# s4.net
KiCad netlist of a schematic drawn in Altium Designer
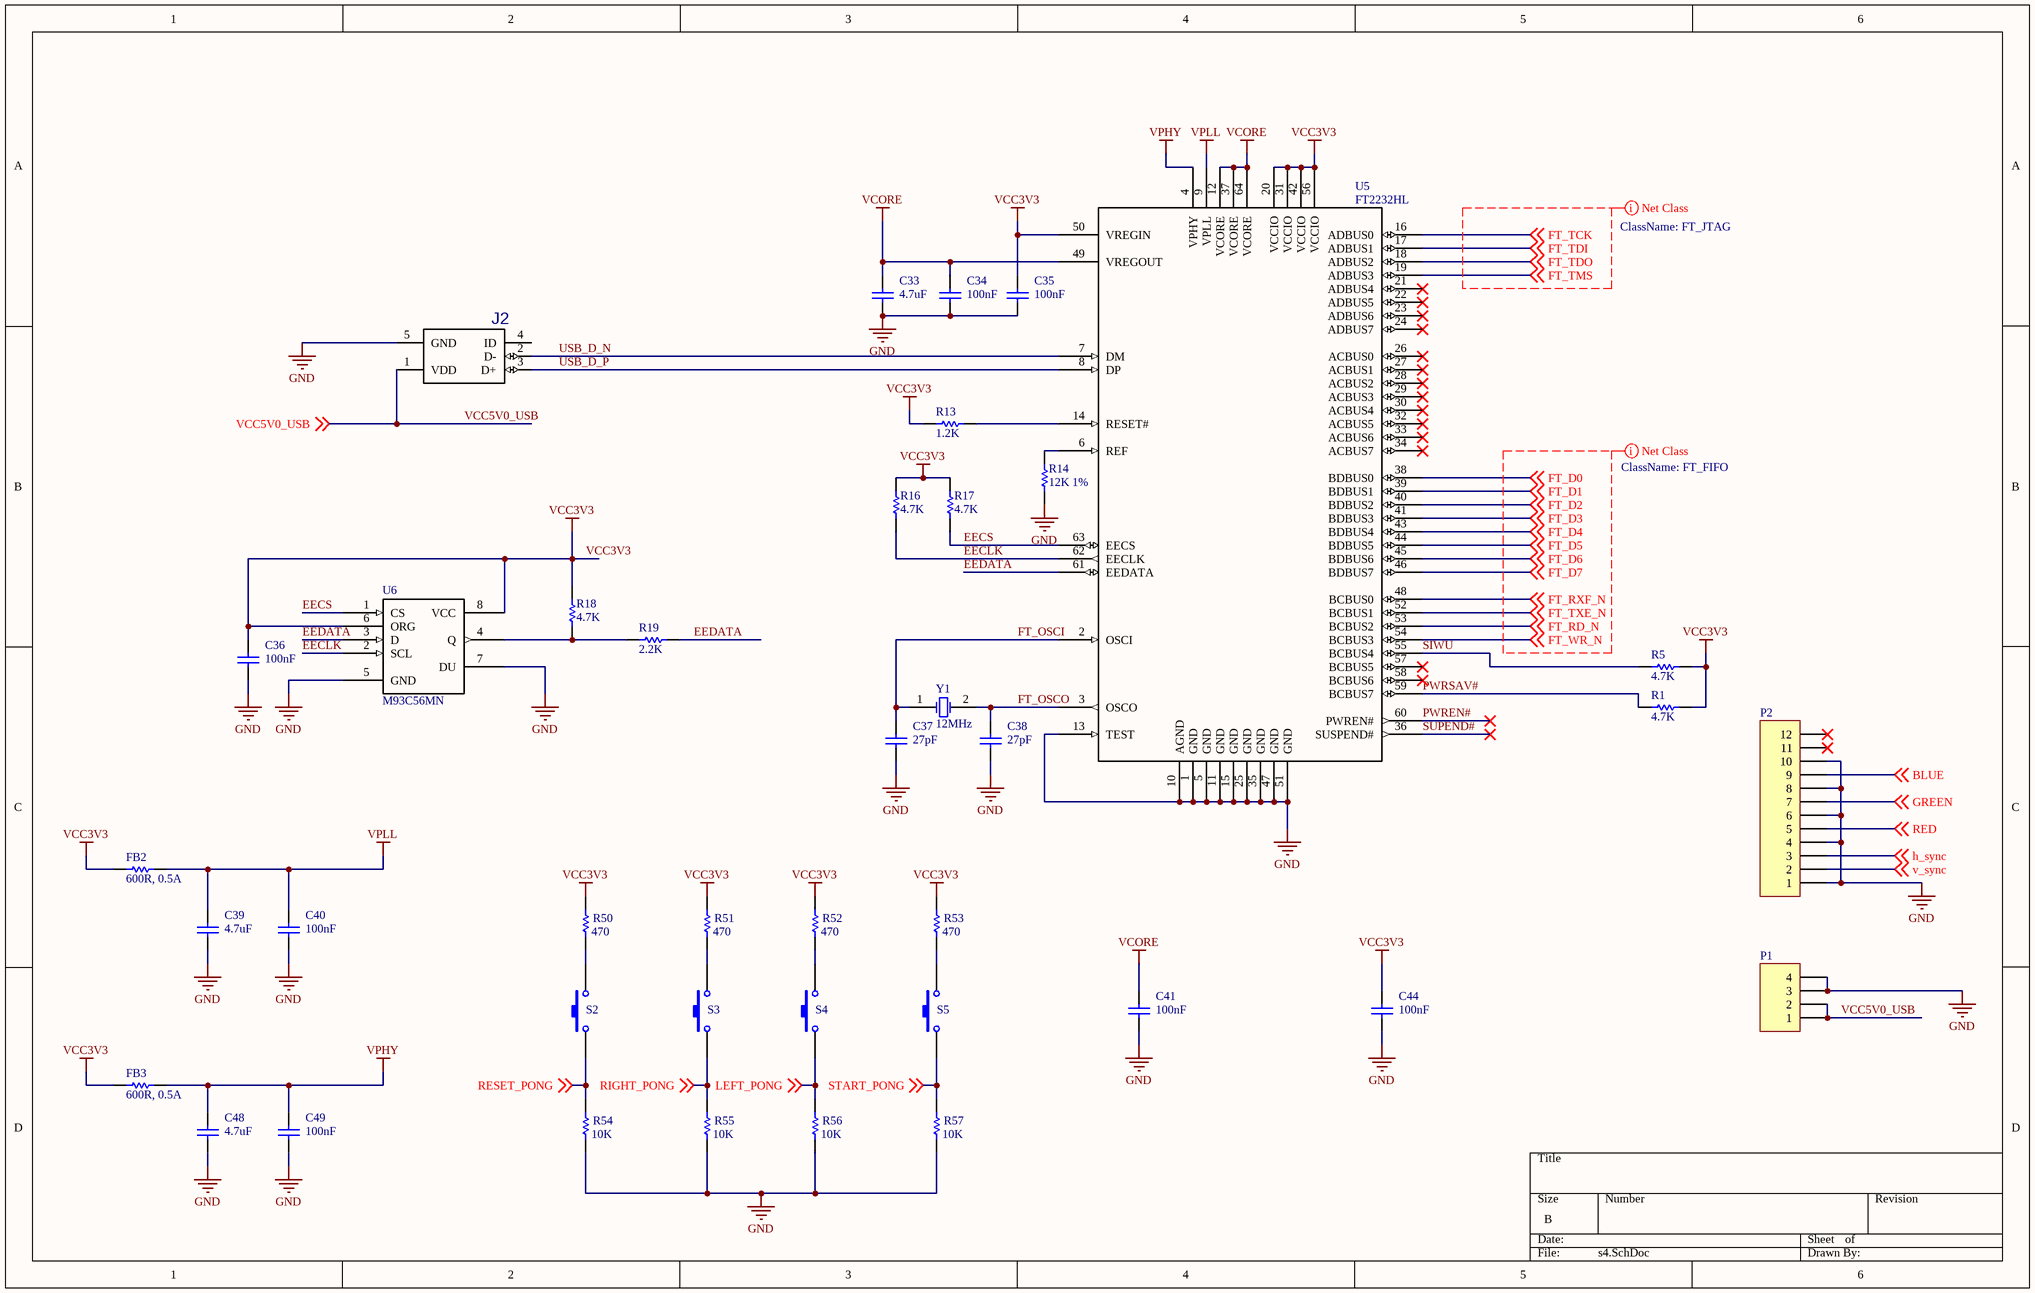
[diagram p0: s4.SchDoc]

(export (version "E")
  (design (tool "Eeschema 10.0.6"))
  (components
    (comp (ref "C33")
      (value "4.7uF")
      (footprint "0805 CAP")
      (description "Capacitor")
      (fields (field (name "Comment") "Cap") (field (name "PUBLISHER") "Altium Limited"))
      (libsource (lib "Miscellaneous Devices") (part "Cap"))
    )
    (comp (ref "C34")
      (value "100nF")
      (footprint "0805 CAP")
      (description "Capacitor")
      (fields (field (name "Comment") "Cap") (field (name "PUBLISHER") "Altium Limited"))
      (libsource (lib "Miscellaneous Devices") (part "Cap"))
    )
    (comp (ref "C35")
      (value "100nF")
      (footprint "0805 CAP")
      (description "Capacitor")
      (fields (field (name "Comment") "Cap") (field (name "PUBLISHER") "Altium Limited"))
      (libsource (lib "Miscellaneous Devices") (part "Cap"))
    )
    (comp (ref "C36")
      (value "100nF")
      (footprint "0805 CAP")
      (description "Capacitor")
      (fields (field (name "Comment") "27pF") (field (name "PUBLISHER") "Altium Limited"))
      (libsource (lib "Miscellaneous Devices") (part "Cap"))
    )
    (comp (ref "C37")
      (value "27pF")
      (footprint "0805 CAP")
      (description "Capacitor")
      (fields (field (name "PUBLISHER") "Altium Limited"))
      (libsource (lib "Miscellaneous Devices") (part "Cap"))
    )
    (comp (ref "C38")
      (value "27pF")
      (footprint "0805 CAP")
      (description "Capacitor")
      (fields (field (name "Comment") "Cap") (field (name "PUBLISHER") "Altium Limited"))
      (libsource (lib "Miscellaneous Devices") (part "Cap"))
    )
    (comp (ref "C39")
      (value "4.7uF")
      (footprint "0805 CAP")
      (description "Capacitor")
      (fields (field (name "Comment") "27pF") (field (name "PUBLISHER") "Altium Limited"))
      (libsource (lib "Miscellaneous Devices") (part "Cap"))
    )
    (comp (ref "C40")
      (value "100nF")
      (footprint "0805 CAP")
      (description "Capacitor")
      (fields (field (name "Comment") "27pF") (field (name "PUBLISHER") "Altium Limited"))
      (libsource (lib "Miscellaneous Devices") (part "Cap"))
    )
    (comp (ref "C41")
      (value "100nF")
      (footprint "0805 CAP")
      (description "Capacitor")
      (fields (field (name "Comment") "Cap") (field (name "PUBLISHER") "Altium Limited"))
      (libsource (lib "Miscellaneous Devices") (part "Cap"))
    )
    (comp (ref "C44")
      (value "100nF")
      (footprint "0805 CAP")
      (description "Capacitor")
      (fields (field (name "Comment") "Cap") (field (name "PUBLISHER") "Altium Limited"))
      (libsource (lib "Miscellaneous Devices") (part "Cap"))
    )
    (comp (ref "C48")
      (value "4.7uF")
      (footprint "0805 CAP")
      (description "Capacitor")
      (fields (field (name "Comment") "27pF") (field (name "PUBLISHER") "Altium Limited"))
      (libsource (lib "Miscellaneous Devices") (part "Cap"))
    )
    (comp (ref "C49")
      (value "100nF")
      (footprint "0805 CAP")
      (description "Capacitor")
      (fields (field (name "Comment") "27pF") (field (name "PUBLISHER") "Altium Limited"))
      (libsource (lib "Miscellaneous Devices") (part "Cap"))
    )
    (comp (ref "FB2")
      (value "600R, 0.5A")
      (footprint "0805 RES")
      (description "Resistor")
      (fields (field (name "Comment") "Res1") (field (name "PUBLISHER") "Altium Limited"))
      (libsource (lib "Miscellaneous Devices") (part "Res1"))
    )
    (comp (ref "FB3")
      (value "600R, 0.5A")
      (footprint "0805 RES")
      (description "Resistor")
      (fields (field (name "Comment") "Res1") (field (name "PUBLISHER") "Altium Limited"))
      (libsource (lib "Miscellaneous Devices") (part "Res1"))
    )
    (comp (ref "J2")
      (value "105017-0001")
      (footprint "MOLEX_105017-0001")
      (description "Conn USB Type B M 5 POS 0.65mm Solder RA Thru-Hole 5 Terminal 1 Port Embossed T/R")
      (fields (field (name "MF") "Molex"))
      (libsource (lib "105017-0001") (part "105017-0001"))
    )
    (comp (ref "P1")
      (value "MHDR1X4")
      (footprint "4 PIN")
      (description "Header, 4-Pin")
      (fields (field (name "PUBLISHER") "Altium Limited"))
      (libsource (lib "Miscellaneous Connectors") (part "MHDR1X4"))
    )
    (comp (ref "P2")
      (value "MHDR1X12")
      (footprint "12 PIN")
      (description "Header, 12-Pin")
      (fields (field (name "PUBLISHER") "Altium Limited"))
      (libsource (lib "Miscellaneous Connectors") (part "MHDR1X12"))
    )
    (comp (ref "R1")
      (value "4.7K")
      (footprint "0805 RES")
      (description "Resistor")
      (fields (field (name "Comment") "Res1") (field (name "PUBLISHER") "Altium Limited"))
      (libsource (lib "Miscellaneous Devices") (part "Res1"))
    )
    (comp (ref "R5")
      (value "4.7K")
      (footprint "0805 RES")
      (description "Resistor")
      (fields (field (name "Comment") "Res1") (field (name "PUBLISHER") "Altium Limited"))
      (libsource (lib "Miscellaneous Devices") (part "Res1"))
    )
    (comp (ref "R13")
      (value "1.2K")
      (footprint "0805 RES")
      (description "Resistor")
      (fields (field (name "Comment") "Res1") (field (name "PUBLISHER") "Altium Limited"))
      (libsource (lib "Miscellaneous Devices") (part "Res1"))
    )
    (comp (ref "R14")
      (value "12K 1%")
      (footprint "0805 RES")
      (description "Resistor")
      (fields (field (name "Comment") "Res1") (field (name "PUBLISHER") "Altium Limited"))
      (libsource (lib "Miscellaneous Devices") (part "Res1"))
    )
    (comp (ref "R16")
      (value "4.7K")
      (footprint "0805 RES")
      (description "Resistor")
      (fields (field (name "Comment") "Res1") (field (name "PUBLISHER") "Altium Limited"))
      (libsource (lib "Miscellaneous Devices") (part "Res1"))
    )
    (comp (ref "R17")
      (value "4.7K")
      (footprint "0805 RES")
      (description "Resistor")
      (fields (field (name "Comment") "Res1") (field (name "PUBLISHER") "Altium Limited"))
      (libsource (lib "Miscellaneous Devices") (part "Res1"))
    )
    (comp (ref "R18")
      (value "4.7K")
      (footprint "0805 RES")
      (description "Resistor")
      (fields (field (name "Comment") "Res1") (field (name "PUBLISHER") "Altium Limited"))
      (libsource (lib "Miscellaneous Devices") (part "Res1"))
    )
    (comp (ref "R19")
      (value "2.2K")
      (footprint "0805 RES")
      (description "Resistor")
      (fields (field (name "Comment") "Res1") (field (name "PUBLISHER") "Altium Limited"))
      (libsource (lib "Miscellaneous Devices") (part "Res1"))
    )
    (comp (ref "R50")
      (value "470")
      (footprint "0805 RES")
      (description "Resistor")
      (fields (field (name "Comment") "Res1") (field (name "PUBLISHER") "Altium Limited"))
      (libsource (lib "Miscellaneous Devices") (part "Res1"))
    )
    (comp (ref "R51")
      (value "470")
      (footprint "0805 RES")
      (description "Resistor")
      (fields (field (name "Comment") "Res1") (field (name "PUBLISHER") "Altium Limited"))
      (libsource (lib "Miscellaneous Devices") (part "Res1"))
    )
    (comp (ref "R52")
      (value "470")
      (footprint "0805 RES")
      (description "Resistor")
      (fields (field (name "Comment") "Res1") (field (name "PUBLISHER") "Altium Limited"))
      (libsource (lib "Miscellaneous Devices") (part "Res1"))
    )
    (comp (ref "R53")
      (value "470")
      (footprint "0805 RES")
      (description "Resistor")
      (fields (field (name "Comment") "Res1") (field (name "PUBLISHER") "Altium Limited"))
      (libsource (lib "Miscellaneous Devices") (part "Res1"))
    )
    (comp (ref "R54")
      (value "10K")
      (footprint "0805 RES")
      (description "Resistor")
      (fields (field (name "Comment") "Res1") (field (name "PUBLISHER") "Altium Limited"))
      (libsource (lib "Miscellaneous Devices") (part "Res1"))
    )
    (comp (ref "R55")
      (value "10K")
      (footprint "0805 RES")
      (description "Resistor")
      (fields (field (name "Comment") "Res1") (field (name "PUBLISHER") "Altium Limited"))
      (libsource (lib "Miscellaneous Devices") (part "Res1"))
    )
    (comp (ref "R56")
      (value "10K")
      (footprint "0805 RES")
      (description "Resistor")
      (fields (field (name "Comment") "Res1") (field (name "PUBLISHER") "Altium Limited"))
      (libsource (lib "Miscellaneous Devices") (part "Res1"))
    )
    (comp (ref "R57")
      (value "10K")
      (footprint "0805 RES")
      (description "Resistor")
      (fields (field (name "Comment") "Res1") (field (name "PUBLISHER") "Altium Limited"))
      (libsource (lib "Miscellaneous Devices") (part "Res1"))
    )
    (comp (ref "S2")
      (value "SW-PB")
      (footprint "Tack Switch")
      (description "Switch")
      (fields (field (name "PUBLISHER") "Altium Limited"))
      (libsource (lib "Miscellaneous Devices") (part "SW-PB"))
    )
    (comp (ref "S3")
      (value "SW-PB")
      (footprint "Tack Switch")
      (description "Switch")
      (fields (field (name "PUBLISHER") "Altium Limited"))
      (libsource (lib "Miscellaneous Devices") (part "SW-PB"))
    )
    (comp (ref "S4")
      (value "SW-PB")
      (footprint "Tack Switch")
      (description "Switch")
      (fields (field (name "PUBLISHER") "Altium Limited"))
      (libsource (lib "Miscellaneous Devices") (part "SW-PB"))
    )
    (comp (ref "S5")
      (value "SW-PB")
      (footprint "Tack Switch")
      (description "Switch")
      (fields (field (name "PUBLISHER") "Altium Limited"))
      (libsource (lib "Miscellaneous Devices") (part "SW-PB"))
    )
    (comp (ref "U5") (value "FT2232HL") (footprint "LQFP64") (libsource (lib "Schlib1") (part "FT2232HL")))
    (comp (ref "U6")
      (value "M93C56MN")
      (footprint "SOIC127P600X175-8N")
      (libsource (lib "Schlib1") (part "M93C56MN"))
    )
    (comp (ref "Y1")
      (value "12MHz")
      (footprint "XTAL1170X500X450")
      (description "Crystal Oscillator")
      (fields (field (name "PUBLISHER") "Altium Limited"))
      (libsource (lib "Miscellaneous Devices") (part "XTAL"))
    )
  )
  (nets
    (net (code "1") (name "/EECLK") (class "Default")
      (node (ref "R16") (pin "2") (pinfunction "2_2") (pintype "passive"))
      (node (ref "U5") (pin "62") (pinfunction "EECLK_62") (pintype "output"))
      (node (ref "U6") (pin "2") (pinfunction "SCL_2") (pintype "input"))
    )
    (net (code "2") (name "/EECS") (class "Default")
      (node (ref "R17") (pin "2") (pinfunction "2_2") (pintype "passive"))
      (node (ref "U5") (pin "63") (pinfunction "EECS_63") (pintype "bidirectional"))
      (node (ref "U6") (pin "1") (pinfunction "CS_1") (pintype "input"))
    )
    (net (code "3") (name "/EEDATA") (class "Default")
      (node (ref "R19") (pin "2") (pinfunction "2_2") (pintype "passive"))
      (node (ref "U5") (pin "61") (pinfunction "EEDATA_61") (pintype "bidirectional"))
      (node (ref "U6") (pin "3") (pinfunction "D_3") (pintype "input"))
    )
    (net (code "4") (name "/FT_OSCI") (class "Default")
      (node (ref "C37") (pin "2") (pinfunction "2_2") (pintype "passive"))
      (node (ref "U5") (pin "2") (pinfunction "OSCI_2") (pintype "input"))
      (node (ref "Y1") (pin "1") (pinfunction "OSC1_1") (pintype "passive"))
    )
    (net (code "5") (name "/FT_OSCO") (class "Default")
      (node (ref "C38") (pin "2") (pinfunction "2_2") (pintype "passive"))
      (node (ref "U5") (pin "3") (pinfunction "OSCO_3") (pintype "output"))
      (node (ref "Y1") (pin "2") (pinfunction "OSC2_2") (pintype "passive"))
    )
    (net (code "6") (name "/PWREN#") (class "Default")
      (node (ref "U5") (pin "60") (pinfunction "PWREN#_60") (pintype "output+no_connect"))
    )
    (net (code "7") (name "/PWRSAV#") (class "Default")
      (node (ref "R1") (pin "2") (pinfunction "2_2") (pintype "passive"))
      (node (ref "U5") (pin "59") (pinfunction "BCBUS7_59") (pintype "bidirectional"))
    )
    (net (code "8") (name "/SIWU") (class "Default")
      (node (ref "R5") (pin "2") (pinfunction "2_2") (pintype "passive"))
      (node (ref "U5") (pin "55") (pinfunction "BCBUS4_55") (pintype "bidirectional"))
    )
    (net (code "9") (name "/SUPEND#") (class "Default")
      (node (ref "U5") (pin "36") (pinfunction "SUSPEND#_36") (pintype "output+no_connect"))
    )
    (net (code "10") (name "/USB_D_N") (class "Default")
      (node (ref "J2") (pin "2") (pinfunction "D-_2") (pintype "bidirectional"))
      (node (ref "U5") (pin "7") (pinfunction "DM_7") (pintype "input"))
    )
    (net (code "11") (name "/USB_D_P") (class "Default")
      (node (ref "J2") (pin "3") (pinfunction "D+_3") (pintype "bidirectional"))
      (node (ref "U5") (pin "8") (pinfunction "DP_8") (pintype "input"))
    )
    (net (code "12") (name "BLUE") (class "Default")
      (node (ref "P2") (pin "9") (pinfunction "9_9") (pintype "passive"))
    )
    (net (code "13") (name "FT_D0") (class "Default")
      (node (ref "U5") (pin "38") (pinfunction "BDBUS0_38") (pintype "bidirectional"))
    )
    (net (code "14") (name "FT_D1") (class "Default")
      (node (ref "U5") (pin "39") (pinfunction "BDBUS1_39") (pintype "bidirectional"))
    )
    (net (code "15") (name "FT_D2") (class "Default")
      (node (ref "U5") (pin "40") (pinfunction "BDBUS2_40") (pintype "bidirectional"))
    )
    (net (code "16") (name "FT_D3") (class "Default")
      (node (ref "U5") (pin "41") (pinfunction "BDBUS3_41") (pintype "bidirectional"))
    )
    (net (code "17") (name "FT_D4") (class "Default")
      (node (ref "U5") (pin "43") (pinfunction "BDBUS4_43") (pintype "bidirectional"))
    )
    (net (code "18") (name "FT_D5") (class "Default")
      (node (ref "U5") (pin "44") (pinfunction "BDBUS5_44") (pintype "bidirectional"))
    )
    (net (code "19") (name "FT_D6") (class "Default")
      (node (ref "U5") (pin "45") (pinfunction "BDBUS6_45") (pintype "bidirectional"))
    )
    (net (code "20") (name "FT_D7") (class "Default")
      (node (ref "U5") (pin "46") (pinfunction "BDBUS7_46") (pintype "bidirectional"))
    )
    (net (code "21") (name "FT_RD_N") (class "Default")
      (node (ref "U5") (pin "53") (pinfunction "BCBUS2_53") (pintype "bidirectional"))
    )
    (net (code "22") (name "FT_RXF_N") (class "Default")
      (node (ref "U5") (pin "48") (pinfunction "BCBUS0_48") (pintype "bidirectional"))
    )
    (net (code "23") (name "FT_TCK") (class "Default")
      (node (ref "U5") (pin "16") (pinfunction "ADBUS0_16") (pintype "bidirectional"))
    )
    (net (code "24") (name "FT_TDI") (class "Default")
      (node (ref "U5") (pin "17") (pinfunction "ADBUS1_17") (pintype "bidirectional"))
    )
    (net (code "25") (name "FT_TDO") (class "Default")
      (node (ref "U5") (pin "18") (pinfunction "ADBUS2_18") (pintype "bidirectional"))
    )
    (net (code "26") (name "FT_TMS") (class "Default")
      (node (ref "U5") (pin "19") (pinfunction "ADBUS3_19") (pintype "bidirectional"))
    )
    (net (code "27") (name "FT_TXE_N") (class "Default")
      (node (ref "U5") (pin "52") (pinfunction "BCBUS1_52") (pintype "bidirectional"))
    )
    (net (code "28") (name "FT_WR_N") (class "Default")
      (node (ref "U5") (pin "54") (pinfunction "BCBUS3_54") (pintype "bidirectional"))
    )
    (net (code "29") (name "GND") (class "Default")
      (node (ref "C33") (pin "1") (pinfunction "1_1") (pintype "passive"))
      (node (ref "C34") (pin "1") (pinfunction "1_1") (pintype "passive"))
      (node (ref "C35") (pin "1") (pinfunction "1_1") (pintype "passive"))
      (node (ref "C36") (pin "1") (pinfunction "1_1") (pintype "passive"))
      (node (ref "C37") (pin "1") (pinfunction "1_1") (pintype "passive"))
      (node (ref "C38") (pin "1") (pinfunction "1_1") (pintype "passive"))
      (node (ref "C39") (pin "1") (pinfunction "1_1") (pintype "passive"))
      (node (ref "C40") (pin "1") (pinfunction "1_1") (pintype "passive"))
      (node (ref "C41") (pin "1") (pinfunction "1_1") (pintype "passive"))
      (node (ref "C44") (pin "1") (pinfunction "1_1") (pintype "passive"))
      (node (ref "C48") (pin "1") (pinfunction "1_1") (pintype "passive"))
      (node (ref "C49") (pin "1") (pinfunction "1_1") (pintype "passive"))
      (node (ref "J2") (pin "5") (pinfunction "GND_5") (pintype "power_in"))
      (node (ref "P1") (pin "3") (pinfunction "3_3") (pintype "passive"))
      (node (ref "P1") (pin "4") (pinfunction "4_4") (pintype "passive"))
      (node (ref "P2") (pin "1") (pinfunction "1_1") (pintype "passive"))
      (node (ref "P2") (pin "10") (pinfunction "10_10") (pintype "passive"))
      (node (ref "P2") (pin "4") (pinfunction "4_4") (pintype "passive"))
      (node (ref "P2") (pin "6") (pinfunction "6_6") (pintype "passive"))
      (node (ref "P2") (pin "8") (pinfunction "8_8") (pintype "passive"))
      (node (ref "R14") (pin "2") (pinfunction "2_2") (pintype "passive"))
      (node (ref "R54") (pin "1") (pinfunction "1_1") (pintype "passive"))
      (node (ref "R55") (pin "1") (pinfunction "1_1") (pintype "passive"))
      (node (ref "R56") (pin "1") (pinfunction "1_1") (pintype "passive"))
      (node (ref "R57") (pin "1") (pinfunction "1_1") (pintype "passive"))
      (node (ref "U5") (pin "1") (pinfunction "GND_1") (pintype "passive"))
      (node (ref "U5") (pin "10") (pinfunction "AGND_10") (pintype "passive"))
      (node (ref "U5") (pin "11") (pinfunction "GND_11") (pintype "passive"))
      (node (ref "U5") (pin "13") (pinfunction "TEST_13") (pintype "input"))
      (node (ref "U5") (pin "15") (pinfunction "GND_15") (pintype "passive"))
      (node (ref "U5") (pin "25") (pinfunction "GND_25") (pintype "passive"))
      (node (ref "U5") (pin "35") (pinfunction "GND_35") (pintype "passive"))
      (node (ref "U5") (pin "47") (pinfunction "GND_47") (pintype "passive"))
      (node (ref "U5") (pin "5") (pinfunction "GND_5") (pintype "passive"))
      (node (ref "U5") (pin "51") (pinfunction "GND_51") (pintype "passive"))
      (node (ref "U6") (pin "5") (pinfunction "GND_5") (pintype "passive"))
      (node (ref "U6") (pin "7") (pinfunction "DU_7") (pintype "passive"))
    )
    (net (code "30") (name "GREEN") (class "Default")
      (node (ref "P2") (pin "7") (pinfunction "7_7") (pintype "passive"))
    )
    (net (code "31") (name "LEFT_PONG") (class "Default")
      (node (ref "R56") (pin "2") (pinfunction "2_2") (pintype "passive"))
      (node (ref "S4") (pin "1") (pinfunction "1_1") (pintype "passive"))
    )
    (net (code "32") (name "Net-(R50-Pad1)") (class "Default")
      (node (ref "R50") (pin "1") (pinfunction "1_1") (pintype "passive"))
      (node (ref "S2") (pin "2") (pinfunction "2_2") (pintype "passive"))
    )
    (net (code "33") (name "Net-(R51-Pad1)") (class "Default")
      (node (ref "R51") (pin "1") (pinfunction "1_1") (pintype "passive"))
      (node (ref "S3") (pin "2") (pinfunction "2_2") (pintype "passive"))
    )
    (net (code "34") (name "Net-(R52-Pad1)") (class "Default")
      (node (ref "R52") (pin "1") (pinfunction "1_1") (pintype "passive"))
      (node (ref "S4") (pin "2") (pinfunction "2_2") (pintype "passive"))
    )
    (net (code "35") (name "Net-(R53-Pad1)") (class "Default")
      (node (ref "R53") (pin "1") (pinfunction "1_1") (pintype "passive"))
      (node (ref "S5") (pin "2") (pinfunction "2_2") (pintype "passive"))
    )
    (net (code "36") (name "Net-(U5-REF)") (class "Default")
      (node (ref "R14") (pin "1") (pinfunction "1_1") (pintype "passive"))
      (node (ref "U5") (pin "6") (pinfunction "REF_6") (pintype "input"))
    )
    (net (code "37") (name "Net-(U5-RESET#)") (class "Default")
      (node (ref "R13") (pin "1") (pinfunction "1_1") (pintype "passive"))
      (node (ref "U5") (pin "14") (pinfunction "RESET#_14") (pintype "input"))
    )
    (net (code "38") (name "Net-(U6-Q)") (class "Default")
      (node (ref "R18") (pin "2") (pinfunction "2_2") (pintype "passive"))
      (node (ref "R19") (pin "1") (pinfunction "1_1") (pintype "passive"))
      (node (ref "U6") (pin "4") (pinfunction "Q_4") (pintype "output"))
    )
    (net (code "39") (name "RED") (class "Default")
      (node (ref "P2") (pin "5") (pinfunction "5_5") (pintype "passive"))
    )
    (net (code "40") (name "RESET_PONG") (class "Default")
      (node (ref "R54") (pin "2") (pinfunction "2_2") (pintype "passive"))
      (node (ref "S2") (pin "1") (pinfunction "1_1") (pintype "passive"))
    )
    (net (code "41") (name "RIGHT_PONG") (class "Default")
      (node (ref "R55") (pin "2") (pinfunction "2_2") (pintype "passive"))
      (node (ref "S3") (pin "1") (pinfunction "1_1") (pintype "passive"))
    )
    (net (code "42") (name "START_PONG") (class "Default")
      (node (ref "R57") (pin "2") (pinfunction "2_2") (pintype "passive"))
      (node (ref "S5") (pin "1") (pinfunction "1_1") (pintype "passive"))
    )
    (net (code "43") (name "VCC3V3") (class "Default")
      (node (ref "C35") (pin "2") (pinfunction "2_2") (pintype "passive"))
      (node (ref "C36") (pin "2") (pinfunction "2_2") (pintype "passive"))
      (node (ref "C44") (pin "2") (pinfunction "2_2") (pintype "passive"))
      (node (ref "FB2") (pin "2") (pinfunction "2_2") (pintype "passive"))
      (node (ref "FB3") (pin "2") (pinfunction "2_2") (pintype "passive"))
      (node (ref "R1") (pin "1") (pinfunction "1_1") (pintype "passive"))
      (node (ref "R13") (pin "2") (pinfunction "2_2") (pintype "passive"))
      (node (ref "R16") (pin "1") (pinfunction "1_1") (pintype "passive"))
      (node (ref "R17") (pin "1") (pinfunction "1_1") (pintype "passive"))
      (node (ref "R18") (pin "1") (pinfunction "1_1") (pintype "passive"))
      (node (ref "R5") (pin "1") (pinfunction "1_1") (pintype "passive"))
      (node (ref "R50") (pin "2") (pinfunction "2_2") (pintype "passive"))
      (node (ref "R51") (pin "2") (pinfunction "2_2") (pintype "passive"))
      (node (ref "R52") (pin "2") (pinfunction "2_2") (pintype "passive"))
      (node (ref "R53") (pin "2") (pinfunction "2_2") (pintype "passive"))
      (node (ref "U5") (pin "20") (pinfunction "VCCIO_20") (pintype "passive"))
      (node (ref "U5") (pin "31") (pinfunction "VCCIO_31") (pintype "passive"))
      (node (ref "U5") (pin "42") (pinfunction "VCCIO_42") (pintype "passive"))
      (node (ref "U5") (pin "50") (pinfunction "VREGIN_50") (pintype "passive"))
      (node (ref "U5") (pin "56") (pinfunction "VCCIO_56") (pintype "passive"))
      (node (ref "U6") (pin "6") (pinfunction "ORG_6") (pintype "passive"))
      (node (ref "U6") (pin "8") (pinfunction "VCC_8") (pintype "passive"))
    )
    (net (code "44") (name "VCC5V0_USB") (class "Default")
      (node (ref "J2") (pin "1") (pinfunction "VDD_1") (pintype "power_in"))
      (node (ref "P1") (pin "1") (pinfunction "1_1") (pintype "passive"))
      (node (ref "P1") (pin "2") (pinfunction "2_2") (pintype "passive"))
    )
    (net (code "45") (name "VCORE") (class "Default")
      (node (ref "C33") (pin "2") (pinfunction "2_2") (pintype "passive"))
      (node (ref "C34") (pin "2") (pinfunction "2_2") (pintype "passive"))
      (node (ref "C41") (pin "2") (pinfunction "2_2") (pintype "passive"))
      (node (ref "U5") (pin "12") (pinfunction "VCORE_12") (pintype "passive"))
      (node (ref "U5") (pin "37") (pinfunction "VCORE_37") (pintype "passive"))
      (node (ref "U5") (pin "49") (pinfunction "VREGOUT_49") (pintype "passive"))
      (node (ref "U5") (pin "64") (pinfunction "VCORE_64") (pintype "passive"))
    )
    (net (code "46") (name "VPHY") (class "Default")
      (node (ref "C48") (pin "2") (pinfunction "2_2") (pintype "passive"))
      (node (ref "C49") (pin "2") (pinfunction "2_2") (pintype "passive"))
      (node (ref "FB3") (pin "1") (pinfunction "1_1") (pintype "passive"))
      (node (ref "U5") (pin "4") (pinfunction "VPHY_4") (pintype "passive"))
    )
    (net (code "47") (name "VPLL") (class "Default")
      (node (ref "C39") (pin "2") (pinfunction "2_2") (pintype "passive"))
      (node (ref "C40") (pin "2") (pinfunction "2_2") (pintype "passive"))
      (node (ref "FB2") (pin "1") (pinfunction "1_1") (pintype "passive"))
      (node (ref "U5") (pin "9") (pinfunction "VPLL_9") (pintype "passive"))
    )
    (net (code "48") (name "h_sync") (class "Default")
      (node (ref "P2") (pin "3") (pinfunction "3_3") (pintype "passive"))
    )
    (net (code "49") (name "unconnected-(J2-ID-Pad4)") (class "Default")
      (node (ref "J2") (pin "4") (pinfunction "ID_4") (pintype "passive"))
    )
    (net (code "50") (name "unconnected-(P2-Pad11)") (class "Default")
      (node (ref "P2") (pin "11") (pinfunction "11_11") (pintype "passive+no_connect"))
    )
    (net (code "51") (name "unconnected-(P2-Pad12)") (class "Default")
      (node (ref "P2") (pin "12") (pinfunction "12_12") (pintype "passive+no_connect"))
    )
    (net (code "52") (name "unconnected-(U5-ACBUS0-Pad26)") (class "Default")
      (node (ref "U5") (pin "26") (pinfunction "ACBUS0_26") (pintype "bidirectional+no_connect"))
    )
    (net (code "53") (name "unconnected-(U5-ACBUS1-Pad27)") (class "Default")
      (node (ref "U5") (pin "27") (pinfunction "ACBUS1_27") (pintype "bidirectional+no_connect"))
    )
    (net (code "54") (name "unconnected-(U5-ACBUS2-Pad28)") (class "Default")
      (node (ref "U5") (pin "28") (pinfunction "ACBUS2_28") (pintype "bidirectional+no_connect"))
    )
    (net (code "55") (name "unconnected-(U5-ACBUS3-Pad29)") (class "Default")
      (node (ref "U5") (pin "29") (pinfunction "ACBUS3_29") (pintype "bidirectional+no_connect"))
    )
    (net (code "56") (name "unconnected-(U5-ACBUS4-Pad30)") (class "Default")
      (node (ref "U5") (pin "30") (pinfunction "ACBUS4_30") (pintype "bidirectional+no_connect"))
    )
    (net (code "57") (name "unconnected-(U5-ACBUS5-Pad32)") (class "Default")
      (node (ref "U5") (pin "32") (pinfunction "ACBUS5_32") (pintype "bidirectional+no_connect"))
    )
    (net (code "58") (name "unconnected-(U5-ACBUS6-Pad33)") (class "Default")
      (node (ref "U5") (pin "33") (pinfunction "ACBUS6_33") (pintype "bidirectional+no_connect"))
    )
    (net (code "59") (name "unconnected-(U5-ACBUS7-Pad34)") (class "Default")
      (node (ref "U5") (pin "34") (pinfunction "ACBUS7_34") (pintype "bidirectional+no_connect"))
    )
    (net (code "60") (name "unconnected-(U5-ADBUS4-Pad21)") (class "Default")
      (node (ref "U5") (pin "21") (pinfunction "ADBUS4_21") (pintype "bidirectional+no_connect"))
    )
    (net (code "61") (name "unconnected-(U5-ADBUS5-Pad22)") (class "Default")
      (node (ref "U5") (pin "22") (pinfunction "ADBUS5_22") (pintype "bidirectional+no_connect"))
    )
    (net (code "62") (name "unconnected-(U5-ADBUS6-Pad23)") (class "Default")
      (node (ref "U5") (pin "23") (pinfunction "ADBUS6_23") (pintype "bidirectional+no_connect"))
    )
    (net (code "63") (name "unconnected-(U5-ADBUS7-Pad24)") (class "Default")
      (node (ref "U5") (pin "24") (pinfunction "ADBUS7_24") (pintype "bidirectional+no_connect"))
    )
    (net (code "64") (name "unconnected-(U5-BCBUS5-Pad57)") (class "Default")
      (node (ref "U5") (pin "57") (pinfunction "BCBUS5_57") (pintype "bidirectional+no_connect"))
    )
    (net (code "65") (name "unconnected-(U5-BCBUS6-Pad58)") (class "Default")
      (node (ref "U5") (pin "58") (pinfunction "BCBUS6_58") (pintype "bidirectional+no_connect"))
    )
    (net (code "66") (name "v_sync") (class "Default")
      (node (ref "P2") (pin "2") (pinfunction "2_2") (pintype "passive"))
    )
  )
)
